# amp.net
KiCad netlist of a schematic drawn in Altium Designer
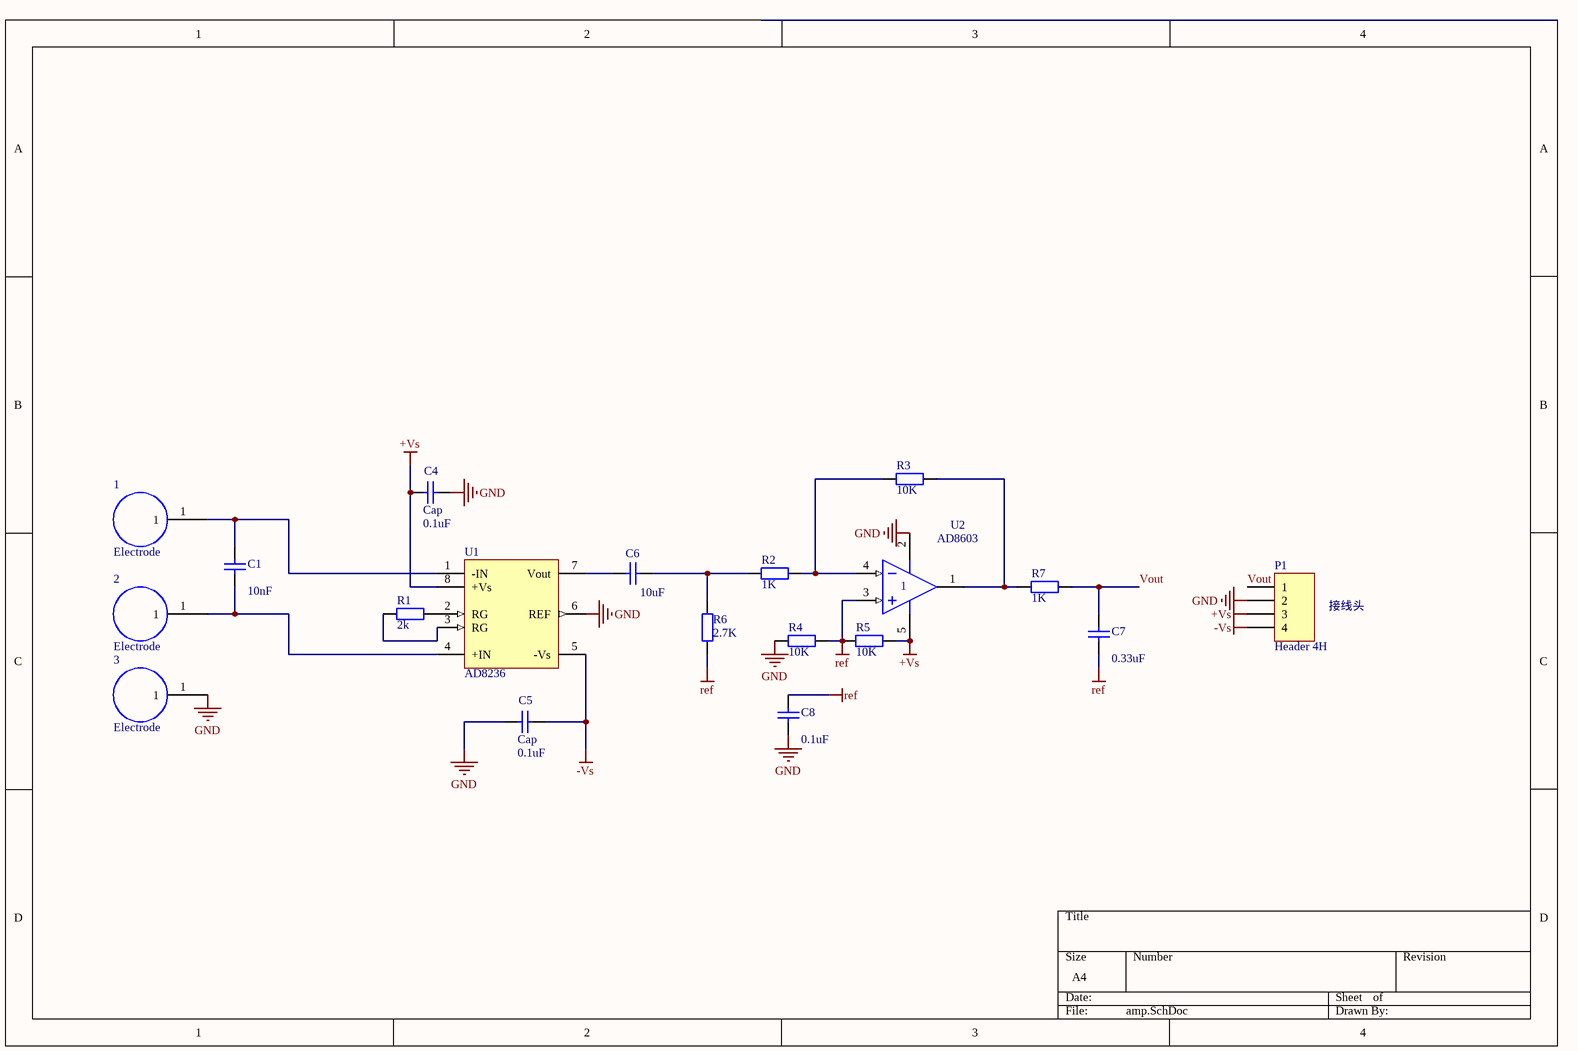
[diagram p0: amp.SchDoc]

(export (version "E")
  (design (tool "Eeschema 10.0.6"))
  (components
    (comp (ref "1")
      (value "Electrode")
      (footprint "elec-diff")
      (libsource (lib "My Sch Library") (part "Electrode"))
    )
    (comp (ref "2")
      (value "Electrode")
      (footprint "elec-diff")
      (libsource (lib "My Sch Library") (part "Electrode"))
    )
    (comp (ref "3")
      (value "Electrode")
      (footprint "elec-ref")
      (libsource (lib "My Sch Library") (part "Electrode"))
    )
    (comp (ref "C1")
      (value "10nF")
      (footprint "0603")
      (description "Capacitor")
      (fields (field (name "PUBLISHER") "Altium Limited"))
      (libsource (lib "Miscellaneous Devices") (part "Cap"))
    )
    (comp (ref "C4")
      (value "Cap")
      (footprint "0603")
      (description "Capacitor")
      (fields (field (name "ALTIUM_VALUE") "0.1uF") (field (name "PUBLISHER") "Altium Limited"))
      (libsource (lib "Miscellaneous Devices") (part "Cap"))
    )
    (comp (ref "C5")
      (value "Cap")
      (footprint "0603")
      (description "Capacitor")
      (fields (field (name "ALTIUM_VALUE") "0.1uF") (field (name "PUBLISHER") "Altium Limited"))
      (libsource (lib "Miscellaneous Devices") (part "Cap"))
    )
    (comp (ref "C6")
      (value "10uF")
      (footprint "0603")
      (description "Capacitor")
      (fields (field (name "PUBLISHER") "Altium Limited"))
      (libsource (lib "Miscellaneous Devices") (part "Cap"))
    )
    (comp (ref "C7")
      (value "0.33uF")
      (footprint "0603")
      (description "Capacitor")
      (fields (field (name "PUBLISHER") "Altium Limited"))
      (libsource (lib "Miscellaneous Devices") (part "Cap"))
    )
    (comp (ref "C8")
      (value "0.1uF")
      (footprint "0603")
      (description "Capacitor")
      (fields (field (name "PUBLISHER") "Altium Limited"))
      (libsource (lib "Miscellaneous Devices") (part "Cap"))
    )
    (comp (ref "P1")
      (value "Header 4H")
      (footprint "BAT3")
      (description "Header, 4-Pin, Right Angle")
      (fields (field (name "PUBLISHER") "Altium Limited"))
      (libsource (lib "Miscellaneous Connectors") (part "Header 4H"))
    )
    (comp (ref "R1")
      (value "2k")
      (footprint "0603")
      (description "Resistor")
      (fields (field (name "PUBLISHER") "Altium Limited"))
      (libsource (lib "Miscellaneous Devices") (part "Res2"))
    )
    (comp (ref "R2")
      (value "1K")
      (footprint "0603")
      (description "Resistor")
      (fields (field (name "PUBLISHER") "Altium Limited"))
      (libsource (lib "") (part "Res2_2"))
    )
    (comp (ref "R3")
      (value "10K")
      (footprint "0603")
      (description "Resistor")
      (fields (field (name "PUBLISHER") "Altium Limited"))
      (libsource (lib "") (part "Res2_2"))
    )
    (comp (ref "R4")
      (value "10K")
      (footprint "0603")
      (description "Resistor")
      (fields (field (name "PUBLISHER") "Altium Limited"))
      (libsource (lib "") (part "Res2_2"))
    )
    (comp (ref "R5")
      (value "10K")
      (footprint "0603")
      (description "Resistor")
      (fields (field (name "PUBLISHER") "Altium Limited"))
      (libsource (lib "") (part "Res2_2"))
    )
    (comp (ref "R6")
      (value "2.7K")
      (footprint "0603")
      (description "Resistor")
      (fields (field (name "PUBLISHER") "Altium Limited"))
      (libsource (lib "") (part "Res2_1"))
    )
    (comp (ref "R7")
      (value "1K")
      (footprint "0603")
      (description "Resistor")
      (fields (field (name "PUBLISHER") "Altium Limited"))
      (libsource (lib "") (part "Res2_2"))
    )
    (comp (ref "U1")
      (value "AD8236")
      (footprint "MSOP-8")
      (description "Precision, Low-Power Instrumentation Amplifiers")
      (fields (field (name "PUBLISHER") "Altium Limited"))
      (libsource (lib "BB Instrumentation Amplifier") (part "INA128UA"))
    )
    (comp (ref "U2")
      (value "AD8603")
      (footprint "SOT23-5AM")
      (libsource (lib "My Sch Library") (part "AD8603"))
    )
  )
  (nets
    (net (code "1") (name "+Vs") (class "Default")
      (node (ref "C4") (pin "1") (pinfunction "1_1") (pintype "passive"))
      (node (ref "P1") (pin "3") (pinfunction "3_3") (pintype "passive"))
      (node (ref "R5") (pin "2") (pinfunction "2_2") (pintype "passive"))
      (node (ref "U1") (pin "8") (pinfunction "+Vs_8") (pintype "passive"))
      (node (ref "U2") (pin "5") (pinfunction "V-_5") (pintype "power_in"))
    )
    (net (code "2") (name "-Vs") (class "Default")
      (node (ref "C5") (pin "2") (pinfunction "2_2") (pintype "passive"))
      (node (ref "P1") (pin "4") (pinfunction "4_4") (pintype "passive"))
      (node (ref "U1") (pin "5") (pinfunction "-Vs_5") (pintype "passive"))
    )
    (net (code "3") (name "/Vout") (class "Default")
      (node (ref "C7") (pin "2") (pinfunction "2_2") (pintype "passive"))
      (node (ref "P1") (pin "1") (pinfunction "1_1") (pintype "passive"))
      (node (ref "R7") (pin "2") (pinfunction "2_2") (pintype "passive"))
    )
    (net (code "4") (name "GND") (class "Default")
      (node (ref "3") (pin "1") (pinfunction "1_1") (pintype "passive"))
      (node (ref "C4") (pin "2") (pinfunction "2_2") (pintype "passive"))
      (node (ref "C5") (pin "1") (pinfunction "1_1") (pintype "passive"))
      (node (ref "C8") (pin "1") (pinfunction "1_1") (pintype "passive"))
      (node (ref "P1") (pin "2") (pinfunction "2_2") (pintype "passive"))
      (node (ref "R4") (pin "1") (pinfunction "1_1") (pintype "passive"))
      (node (ref "U1") (pin "6") (pinfunction "REF_6") (pintype "output"))
      (node (ref "U2") (pin "2") (pinfunction "V+_2") (pintype "power_in"))
    )
    (net (code "5") (name "Net-(C6-Pad1)") (class "Default")
      (node (ref "C6") (pin "1") (pinfunction "1_1") (pintype "passive"))
      (node (ref "R2") (pin "1") (pinfunction "1_1") (pintype "passive"))
      (node (ref "R6") (pin "2") (pinfunction "2_2") (pintype "passive"))
    )
    (net (code "6") (name "Net-(R1-Pad1)") (class "Default")
      (node (ref "R1") (pin "1") (pinfunction "1_1") (pintype "passive"))
      (node (ref "U1") (pin "2") (pinfunction "RG_2") (pintype "input"))
    )
    (net (code "7") (name "Net-(R1-Pad2)") (class "Default")
      (node (ref "R1") (pin "2") (pinfunction "2_2") (pintype "passive"))
      (node (ref "U1") (pin "3") (pinfunction "RG_3") (pintype "input"))
    )
    (net (code "8") (name "Net-(U1-+IN)") (class "Default")
      (node (ref "2") (pin "1") (pinfunction "1_1") (pintype "passive"))
      (node (ref "C1") (pin "1") (pinfunction "1_1") (pintype "passive"))
      (node (ref "U1") (pin "4") (pinfunction "+IN_4") (pintype "power_in"))
    )
    (net (code "9") (name "Net-(U1--IN)") (class "Default")
      (node (ref "1") (pin "1") (pinfunction "1_1") (pintype "passive"))
      (node (ref "C1") (pin "2") (pinfunction "2_2") (pintype "passive"))
      (node (ref "U1") (pin "1") (pinfunction "-IN_1") (pintype "passive"))
    )
    (net (code "10") (name "Net-(U1-Vout)") (class "Default")
      (node (ref "C6") (pin "2") (pinfunction "2_2") (pintype "passive"))
      (node (ref "U1") (pin "7") (pinfunction "Vout_7") (pintype "power_in"))
    )
    (net (code "11") (name "Net-(U2-IN-)") (class "Default")
      (node (ref "R2") (pin "2") (pinfunction "2_2") (pintype "passive"))
      (node (ref "R3") (pin "1") (pinfunction "1_1") (pintype "passive"))
      (node (ref "U2") (pin "4") (pinfunction "IN-_4") (pintype "input"))
    )
    (net (code "12") (name "Net-(U2-OUT)") (class "Default")
      (node (ref "R3") (pin "2") (pinfunction "2_2") (pintype "passive"))
      (node (ref "R7") (pin "1") (pinfunction "1_1") (pintype "passive"))
      (node (ref "U2") (pin "1") (pinfunction "OUT_1") (pintype "passive"))
    )
    (net (code "13") (name "ref") (class "Default")
      (node (ref "C7") (pin "1") (pinfunction "1_1") (pintype "passive"))
      (node (ref "C8") (pin "2") (pinfunction "2_2") (pintype "passive"))
      (node (ref "R4") (pin "2") (pinfunction "2_2") (pintype "passive"))
      (node (ref "R5") (pin "1") (pinfunction "1_1") (pintype "passive"))
      (node (ref "R6") (pin "1") (pinfunction "1_1") (pintype "passive"))
      (node (ref "U2") (pin "3") (pinfunction "IN+_3") (pintype "input"))
    )
  )
)
